# femtoBeacon-BT5_r1_0_1.net
KiCad netlist of a schematic drawn in EAGLE
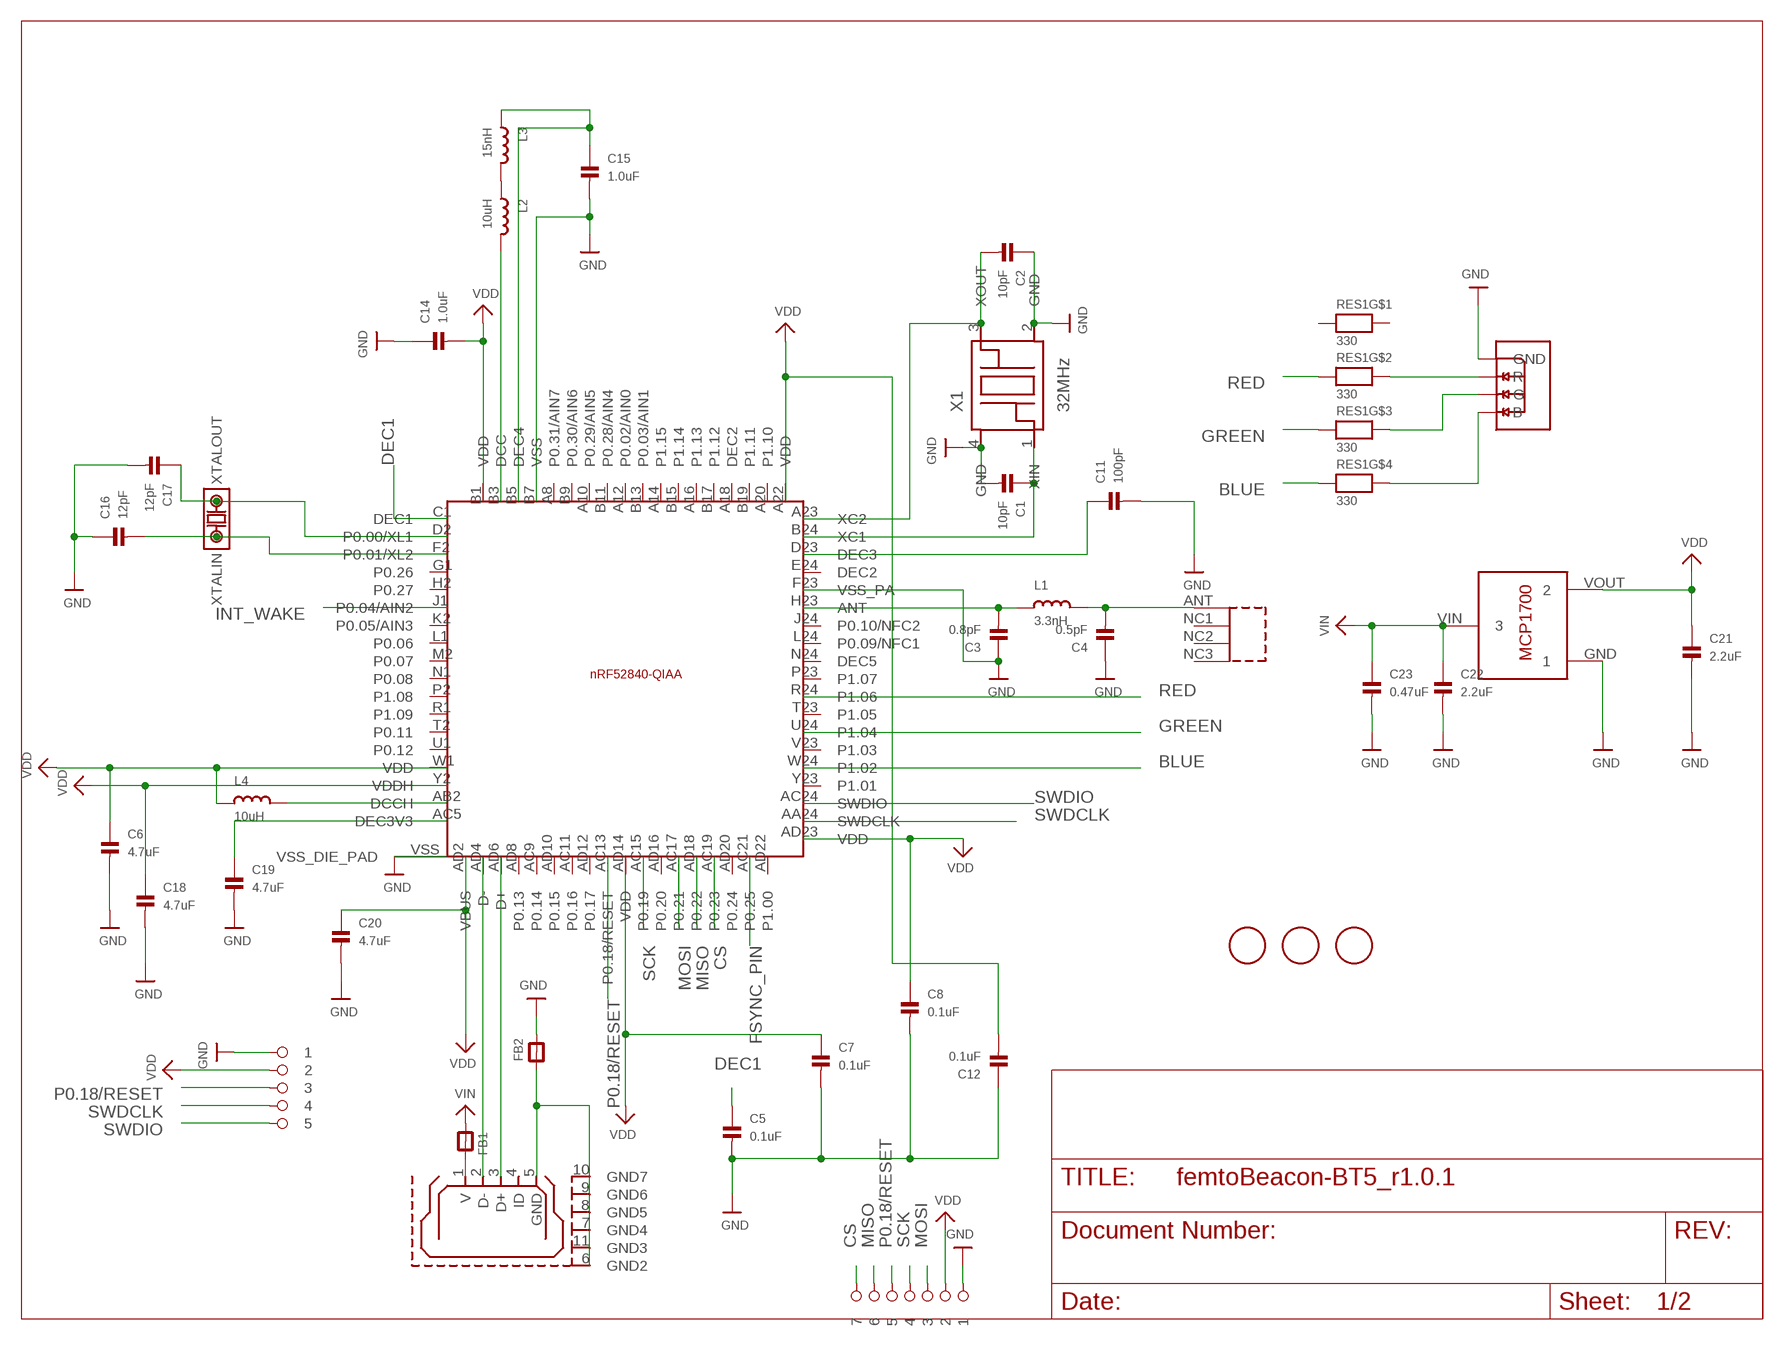
[diagram p0: schematic, sheet 1]
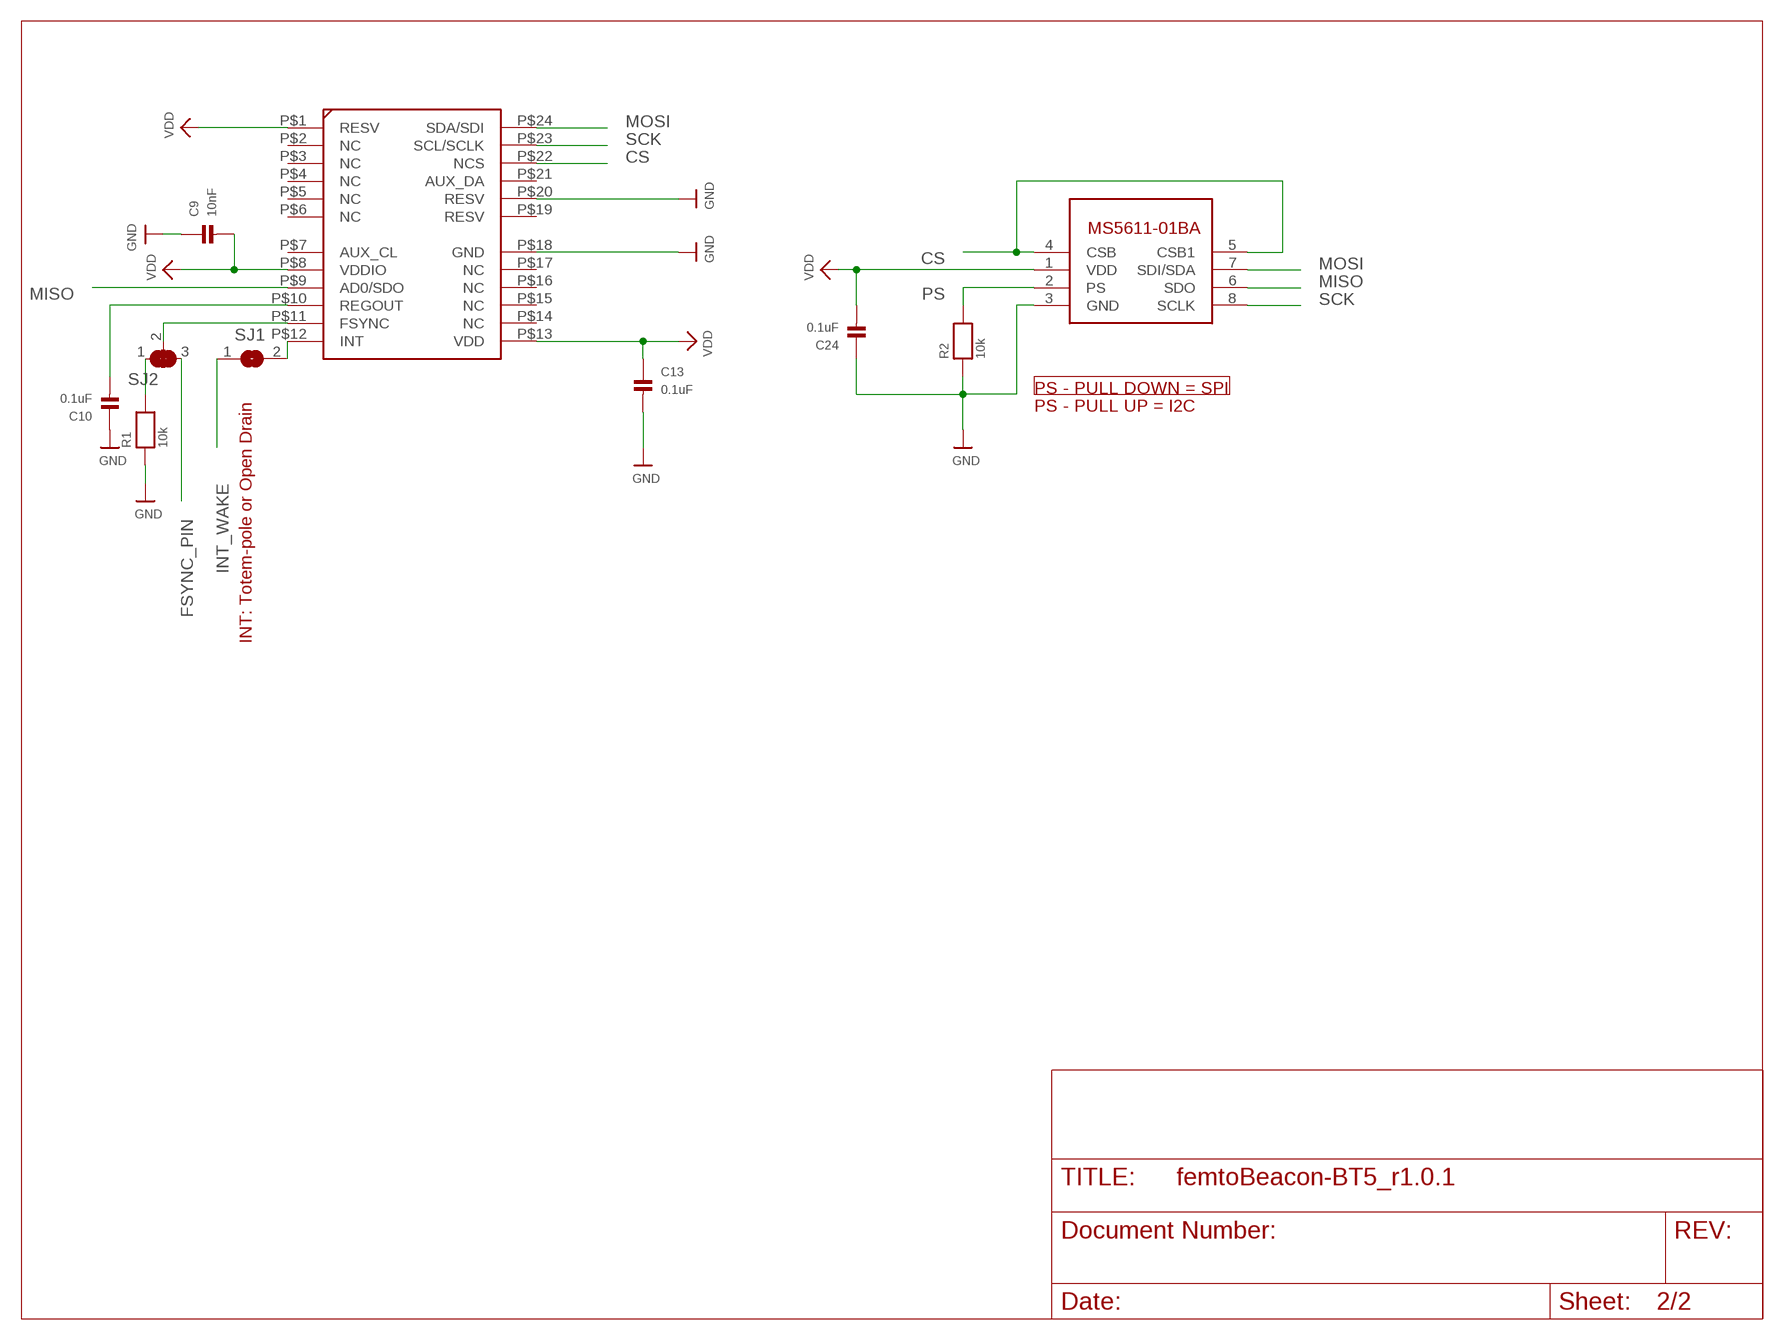
[diagram p1: schematic, sheet 2]

(export (version "E")
  (design (tool "Eeschema 10.0.6"))
  (components
    (comp (ref "ANT")
      (value "0479480001")
      (footprint "eagle-import:0479480001")
      (libsource (lib "eagle-import") (part "0479480001"))
    )
    (comp (ref "C1")
      (value "10pF")
      (footprint "eagle-import:_0402MP")
      (libsource (lib "eagle-import") (part "CAP_CERAMIC_0402MP"))
    )
    (comp (ref "C2")
      (value "10pF")
      (footprint "eagle-import:_0402MP")
      (libsource (lib "eagle-import") (part "CAP_CERAMIC_0402MP"))
    )
    (comp (ref "C3")
      (value "0.8pF")
      (footprint "eagle-import:_0402MP")
      (libsource (lib "eagle-import") (part "CAP_CERAMIC_0402MP"))
    )
    (comp (ref "C4")
      (value "0.5pF")
      (footprint "eagle-import:_0402MP")
      (libsource (lib "eagle-import") (part "CAP_CERAMIC_0402MP"))
    )
    (comp (ref "C5")
      (value "0.1uF")
      (footprint "eagle-import:_0402MP")
      (libsource (lib "eagle-import") (part "CAP_CERAMIC_0402MP"))
    )
    (comp (ref "C6")
      (value "4.7uF")
      (footprint "eagle-import:_0402MP")
      (libsource (lib "eagle-import") (part "CAP_CERAMIC_0402MP"))
    )
    (comp (ref "C7")
      (value "0.1uF")
      (footprint "eagle-import:_0402MP")
      (libsource (lib "eagle-import") (part "CAP_CERAMIC_0402MP"))
    )
    (comp (ref "C8")
      (value "0.1uF")
      (footprint "eagle-import:_0402MP")
      (libsource (lib "eagle-import") (part "CAP_CERAMIC_0402MP"))
    )
    (comp (ref "C11")
      (value "100pF")
      (footprint "eagle-import:_0402MP")
      (libsource (lib "eagle-import") (part "CAP_CERAMIC_0402MP"))
    )
    (comp (ref "C12")
      (value "0.1uF")
      (footprint "eagle-import:_0402MP")
      (libsource (lib "eagle-import") (part "CAP_CERAMIC_0402MP"))
    )
    (comp (ref "C14")
      (value "1.0uF")
      (footprint "eagle-import:_0402MP")
      (libsource (lib "eagle-import") (part "CAP_CERAMIC_0402MP"))
    )
    (comp (ref "C15")
      (value "1.0uF")
      (footprint "eagle-import:_0402MP")
      (libsource (lib "eagle-import") (part "CAP_CERAMIC_0402MP"))
    )
    (comp (ref "C16")
      (value "12pF")
      (footprint "eagle-import:_0402MP")
      (libsource (lib "eagle-import") (part "CAP_CERAMIC_0402MP"))
    )
    (comp (ref "C17")
      (value "12pF")
      (footprint "eagle-import:_0402MP")
      (libsource (lib "eagle-import") (part "CAP_CERAMIC_0402MP"))
    )
    (comp (ref "C18")
      (value "4.7uF")
      (footprint "eagle-import:_0402MP")
      (libsource (lib "eagle-import") (part "CAP_CERAMIC_0402MP"))
    )
    (comp (ref "C19")
      (value "4.7uF")
      (footprint "eagle-import:_0402MP")
      (libsource (lib "eagle-import") (part "CAP_CERAMIC_0402MP"))
    )
    (comp (ref "C20")
      (value "4.7uF")
      (footprint "eagle-import:_0402MP")
      (libsource (lib "eagle-import") (part "CAP_CERAMIC_0402MP"))
    )
    (comp (ref "C21")
      (value "2.2uF")
      (footprint "eagle-import:_0402MP")
      (libsource (lib "eagle-import") (part "CAP_CERAMIC_0402MP"))
    )
    (comp (ref "C22")
      (value "2.2uF")
      (footprint "eagle-import:_0402MP")
      (libsource (lib "eagle-import") (part "CAP_CERAMIC_0402MP"))
    )
    (comp (ref "C23")
      (value "0.47uF")
      (footprint "eagle-import:_0402MP")
      (libsource (lib "eagle-import") (part "CAP_CERAMIC_0402MP"))
    )
    (comp (ref "FB1")
      (value "FERRITE_0603MP")
      (footprint "eagle-import:_0603MP")
      (libsource (lib "eagle-import") (part "FERRITE_0603MP"))
    )
    (comp (ref "FB2")
      (value "FERRITE_0603MP")
      (footprint "eagle-import:_0603MP")
      (libsource (lib "eagle-import") (part "FERRITE_0603MP"))
    )
    (comp (ref "FID1")
      (value "FIDUCIAL")
      (footprint "eagle-import:FIDUCIAL_1MM")
      (libsource (lib "eagle-import") (part "FIDUCIAL"))
    )
    (comp (ref "FID2")
      (value "FIDUCIAL")
      (footprint "eagle-import:FIDUCIAL_1MM")
      (libsource (lib "eagle-import") (part "FIDUCIAL"))
    )
    (comp (ref "FID3")
      (value "FIDUCIAL")
      (footprint "eagle-import:FIDUCIAL_1MM")
      (libsource (lib "eagle-import") (part "FIDUCIAL"))
    )
    (comp (ref "IC")
      (value "NRF52840")
      (footprint "eagle-import:NRF52840")
      (libsource (lib "eagle-import") (part "NRF52840"))
    )
    (comp (ref "L1")
      (value "3.3nH")
      (footprint "eagle-import:_0402MP")
      (libsource (lib "eagle-import") (part "INDUCTOR_0402MP"))
    )
    (comp (ref "L2")
      (value "10uH")
      (footprint "eagle-import:_0402MP")
      (libsource (lib "eagle-import") (part "INDUCTOR_0402MP"))
    )
    (comp (ref "L3")
      (value "15nH")
      (footprint "eagle-import:_0402MP")
      (libsource (lib "eagle-import") (part "INDUCTOR_0402MP"))
    )
    (comp (ref "L4")
      (value "10uH")
      (footprint "eagle-import:_0402MP")
      (libsource (lib "eagle-import") (part "INDUCTOR_0402MP"))
    )
    (comp (ref "LDO_VREG")
      (value "MCP1700T-3302E/TT")
      (footprint "eagle-import:MCP1700T-3302E_TT")
      (libsource (lib "eagle-import") (part "MCP1700T-3302E/TT"))
    )
    (comp (ref "RES1")
      (value "330")
      (footprint "eagle-import:RESPACK_4X0603")
      (fields (field (name "MFN_ID") "741C083331JP"))
      (libsource (lib "eagle-import") (part "RESISTOR_4PACK"))
    )
    (comp (ref "U$1")
      (value "1X5_ROUND")
      (footprint "eagle-import:1X5_ROUND")
      (libsource (lib "eagle-import") (part "1X5_ROUND"))
    )
    (comp (ref "U$7")
      (value "LRTB_R48G")
      (footprint "eagle-import:LRTB_R48G")
      (libsource (lib "eagle-import") (part "LRTB_R48G"))
    )
    (comp (ref "U$27")
      (value "1X7_ROUND")
      (footprint "eagle-import:1X7_ROUND")
      (libsource (lib "eagle-import") (part "1X7_ROUND"))
    )
    (comp (ref "USB")
      (value "USB_MICROB")
      (footprint "eagle-import:USB_MICROB_PACKAGE")
      (libsource (lib "eagle-import") (part "USB_MICROB"))
    )
    (comp (ref "X1")
      (value "32MHz")
      (footprint "eagle-import:FA-128")
      (libsource (lib "eagle-import") (part "FA-128"))
    )
    (comp (ref "X2")
      (value "32.768kHZ")
      (footprint "eagle-import:ABS06-107-32.768KHZ-T")
      (libsource (lib "eagle-import") (part "ABS06-107-32.768KHZ-T"))
    )
    (comp (ref "BARO")
      (value "MS5611-01BA03")
      (footprint "eagle-import:MS5611-01BA03")
      (libsource (lib "eagle-import") (part "MS5611-01BA03"))
    )
    (comp (ref "C9")
      (value "10nF")
      (footprint "eagle-import:_0402MP")
      (libsource (lib "eagle-import") (part "CAP_CERAMIC_0402MP"))
    )
    (comp (ref "C10")
      (value "0.1uF")
      (footprint "eagle-import:_0402MP")
      (libsource (lib "eagle-import") (part "CAP_CERAMIC_0402MP"))
    )
    (comp (ref "C13")
      (value "0.1uF")
      (footprint "eagle-import:_0402MP")
      (libsource (lib "eagle-import") (part "CAP_CERAMIC_0402MP"))
    )
    (comp (ref "C24")
      (value "0.1uF")
      (footprint "eagle-import:_0402MP")
      (libsource (lib "eagle-import") (part "CAP_CERAMIC_0402MP"))
    )
    (comp (ref "IMU")
      (value "MPU-9250")
      (footprint "eagle-import:QFN_3X3MM")
      (libsource (lib "eagle-import") (part "MPU-9250"))
    )
    (comp (ref "R1")
      (value "10k")
      (footprint "eagle-import:_0402MP")
      (libsource (lib "eagle-import") (part "RESISTOR_0402MP"))
    )
    (comp (ref "R2")
      (value "10k")
      (footprint "eagle-import:_0402MP")
      (libsource (lib "eagle-import") (part "RESISTOR_0402MP"))
    )
    (comp (ref "SJ1")
      (value "SOLDERJUMPERCLOSED")
      (footprint "eagle-import:SOLDERJUMPER_CLOSEDWIRE")
      (libsource (lib "eagle-import") (part "SOLDERJUMPERCLOSED"))
    )
    (comp (ref "SJ2")
      (value "SOLDERJUMPER_2WAY")
      (footprint "eagle-import:SOLDERJUMPER_2WAY_OPEN_NOPASTE")
      (libsource (lib "eagle-import") (part "SOLDERJUMPER_2WAY"))
    )
  )
  (nets
    (net (code "1") (name "BLUE") (class "Default")
      (node (ref "IC") (pin "W24") (pinfunction "P1.02_W24") (pintype "bidirectional"))
      (node (ref "RES1") (pin "4") (pinfunction "1_4") (pintype "passive"))
    )
    (net (code "2") (name "CS") (class "Default")
      (node (ref "BARO") (pin "4") (pinfunction "CSB_4") (pintype "bidirectional"))
      (node (ref "BARO") (pin "5") (pinfunction "CSB1_5") (pintype "bidirectional"))
      (node (ref "IC") (pin "AC19") (pinfunction "P0.23_AC19") (pintype "bidirectional"))
      (node (ref "IMU") (pin "P$22") (pinfunction "NCS_P$22") (pintype "bidirectional"))
      (node (ref "U$27") (pin "P$7") (pinfunction "7_P$7") (pintype "bidirectional"))
    )
    (net (code "3") (name "DEC1") (class "Default")
      (node (ref "C5") (pin "1") (pinfunction "P$1_1") (pintype "passive"))
      (node (ref "IC") (pin "C1") (pinfunction "DEC1_C1") (pintype "bidirectional"))
    )
    (net (code "4") (name "FSYNC_PIN") (class "Default")
      (node (ref "IC") (pin "AC21") (pinfunction "P0.25_AC21") (pintype "bidirectional"))
      (node (ref "SJ2") (pin "3") (pinfunction "3_3") (pintype "passive"))
    )
    (net (code "5") (name "GND") (class "Default")
      (node (ref "BARO") (pin "3") (pinfunction "GND_3") (pintype "bidirectional"))
      (node (ref "C1") (pin "2") (pinfunction "P$2_2") (pintype "passive"))
      (node (ref "C10") (pin "1") (pinfunction "P$1_1") (pintype "passive"))
      (node (ref "C11") (pin "2") (pinfunction "P$2_2") (pintype "passive"))
      (node (ref "C12") (pin "1") (pinfunction "P$1_1") (pintype "passive"))
      (node (ref "C13") (pin "2") (pinfunction "P$2_2") (pintype "passive"))
      (node (ref "C14") (pin "1") (pinfunction "P$1_1") (pintype "passive"))
      (node (ref "C15") (pin "2") (pinfunction "P$2_2") (pintype "passive"))
      (node (ref "C16") (pin "1") (pinfunction "P$1_1") (pintype "passive"))
      (node (ref "C17") (pin "2") (pinfunction "P$2_2") (pintype "passive"))
      (node (ref "C18") (pin "2") (pinfunction "P$2_2") (pintype "passive"))
      (node (ref "C19") (pin "2") (pinfunction "P$2_2") (pintype "passive"))
      (node (ref "C2") (pin "1") (pinfunction "P$1_1") (pintype "passive"))
      (node (ref "C20") (pin "2") (pinfunction "P$2_2") (pintype "passive"))
      (node (ref "C21") (pin "2") (pinfunction "P$2_2") (pintype "passive"))
      (node (ref "C22") (pin "2") (pinfunction "P$2_2") (pintype "passive"))
      (node (ref "C23") (pin "2") (pinfunction "P$2_2") (pintype "passive"))
      (node (ref "C24") (pin "1") (pinfunction "P$1_1") (pintype "passive"))
      (node (ref "C3") (pin "1") (pinfunction "P$1_1") (pintype "passive"))
      (node (ref "C4") (pin "1") (pinfunction "P$1_1") (pintype "passive"))
      (node (ref "C5") (pin "2") (pinfunction "P$2_2") (pintype "passive"))
      (node (ref "C6") (pin "2") (pinfunction "P$2_2") (pintype "passive"))
      (node (ref "C7") (pin "2") (pinfunction "P$2_2") (pintype "passive"))
      (node (ref "C8") (pin "2") (pinfunction "P$2_2") (pintype "passive"))
      (node (ref "C9") (pin "1") (pinfunction "P$1_1") (pintype "passive"))
      (node (ref "FB2") (pin "2") (pinfunction "P$2_2") (pintype "passive"))
      (node (ref "IC") (pin "B7") (pinfunction "VSS_B7") (pintype "bidirectional"))
      (node (ref "IC") (pin "F23") (pinfunction "VSS_PA_F23") (pintype "bidirectional"))
      (node (ref "IC") (pin "VSS") (pinfunction "VSS_DIE_PAD_VSS") (pintype "bidirectional"))
      (node (ref "IMU") (pin "P$18") (pinfunction "GND_P$18") (pintype "bidirectional"))
      (node (ref "IMU") (pin "P$20") (pinfunction "RESV_P$20") (pintype "bidirectional"))
      (node (ref "LDO_VREG") (pin "GND") (pinfunction "1_GND") (pintype "bidirectional"))
      (node (ref "R1") (pin "1") (pinfunction "1_1") (pintype "passive"))
      (node (ref "R2") (pin "1") (pinfunction "1_1") (pintype "passive"))
      (node (ref "U$1") (pin "P$1") (pinfunction "1_P$1") (pintype "bidirectional"))
      (node (ref "U$27") (pin "P$1") (pinfunction "1_P$1") (pintype "bidirectional"))
      (node (ref "U$7") (pin "1") (pinfunction "GND_1") (pintype "bidirectional"))
      (node (ref "X1") (pin "2") (pinfunction "GND_2") (pintype "bidirectional"))
      (node (ref "X1") (pin "4") (pinfunction "GND_4") (pintype "bidirectional"))
    )
    (net (code "6") (name "GREEN") (class "Default")
      (node (ref "IC") (pin "U24") (pinfunction "P1.04_U24") (pintype "bidirectional"))
      (node (ref "RES1") (pin "3") (pinfunction "1_3") (pintype "passive"))
    )
    (net (code "7") (name "INT_WAKE") (class "Default")
      (node (ref "IC") (pin "J1") (pinfunction "P0.04/AIN2_J1") (pintype "bidirectional"))
      (node (ref "SJ1") (pin "1") (pinfunction "1_1") (pintype "passive"))
    )
    (net (code "8") (name "MISO") (class "Default")
      (node (ref "BARO") (pin "6") (pinfunction "SDO_6") (pintype "bidirectional"))
      (node (ref "IC") (pin "AD18") (pinfunction "P0.22_AD18") (pintype "bidirectional"))
      (node (ref "IMU") (pin "P$9") (pinfunction "AD0/SDO_P$9") (pintype "bidirectional"))
      (node (ref "U$27") (pin "P$6") (pinfunction "6_P$6") (pintype "bidirectional"))
    )
    (net (code "9") (name "MOSI") (class "Default")
      (node (ref "BARO") (pin "7") (pinfunction "SDI/SDA_7") (pintype "bidirectional"))
      (node (ref "IC") (pin "AC17") (pinfunction "P0.21_AC17") (pintype "bidirectional"))
      (node (ref "IMU") (pin "P$24") (pinfunction "SDA/SDI_P$24") (pintype "bidirectional"))
      (node (ref "U$27") (pin "P$3") (pinfunction "3_P$3") (pintype "bidirectional"))
    )
    (net (code "10") (name "Net-(ANT-1)") (class "Default")
      (node (ref "ANT") (pin "ANT") (pinfunction "1_ANT") (pintype "bidirectional"))
      (node (ref "C4") (pin "2") (pinfunction "P$2_2") (pintype "passive"))
      (node (ref "L1") (pin "2") (pinfunction "2_2") (pintype "passive"))
    )
    (net (code "11") (name "Net-(C1-P$1)") (class "Default")
      (node (ref "C1") (pin "1") (pinfunction "P$1_1") (pintype "passive"))
      (node (ref "IC") (pin "B24") (pinfunction "XC1_B24") (pintype "bidirectional"))
      (node (ref "X1") (pin "1") (pinfunction "XIN_1") (pintype "bidirectional"))
    )
    (net (code "12") (name "Net-(C2-P$2)") (class "Default")
      (node (ref "C2") (pin "2") (pinfunction "P$2_2") (pintype "passive"))
      (node (ref "IC") (pin "A23") (pinfunction "XC2_A23") (pintype "bidirectional"))
      (node (ref "X1") (pin "3") (pinfunction "XOUT_3") (pintype "bidirectional"))
    )
    (net (code "13") (name "Net-(C3-P$2)") (class "Default")
      (node (ref "C3") (pin "2") (pinfunction "P$2_2") (pintype "passive"))
      (node (ref "IC") (pin "H23") (pinfunction "ANT_H23") (pintype "bidirectional"))
      (node (ref "L1") (pin "1") (pinfunction "1_1") (pintype "passive"))
    )
    (net (code "14") (name "Net-(C10-P$2)") (class "Default")
      (node (ref "C10") (pin "2") (pinfunction "P$2_2") (pintype "passive"))
      (node (ref "IMU") (pin "P$10") (pinfunction "REGOUT_P$10") (pintype "bidirectional"))
    )
    (net (code "15") (name "Net-(C11-P$1)") (class "Default")
      (node (ref "C11") (pin "1") (pinfunction "P$1_1") (pintype "passive"))
      (node (ref "IC") (pin "D23") (pinfunction "DEC3_D23") (pintype "bidirectional"))
    )
    (net (code "16") (name "Net-(C15-P$1)") (class "Default")
      (node (ref "C15") (pin "1") (pinfunction "P$1_1") (pintype "passive"))
      (node (ref "IC") (pin "B5") (pinfunction "DEC4_B5") (pintype "bidirectional"))
      (node (ref "L3") (pin "1") (pinfunction "1_1") (pintype "passive"))
    )
    (net (code "17") (name "Net-(C16-P$2)") (class "Default")
      (node (ref "C16") (pin "2") (pinfunction "P$2_2") (pintype "passive"))
      (node (ref "IC") (pin "F2") (pinfunction "P0.01/XL2_F2") (pintype "bidirectional"))
      (node (ref "X2") (pin "1") (pinfunction "XTALIN_1") (pintype "bidirectional"))
    )
    (net (code "18") (name "Net-(C17-P$1)") (class "Default")
      (node (ref "C17") (pin "1") (pinfunction "P$1_1") (pintype "passive"))
      (node (ref "IC") (pin "D2") (pinfunction "P0.00/XL1_D2") (pintype "bidirectional"))
      (node (ref "X2") (pin "2") (pinfunction "XTALOUT_2") (pintype "bidirectional"))
    )
    (net (code "19") (name "Net-(C19-P$1)") (class "Default")
      (node (ref "C19") (pin "1") (pinfunction "P$1_1") (pintype "passive"))
      (node (ref "IC") (pin "AC5") (pinfunction "DEC3V3_AC5") (pintype "bidirectional"))
    )
    (net (code "20") (name "Net-(FB1-P$2)") (class "Default")
      (node (ref "FB1") (pin "2") (pinfunction "P$2_2") (pintype "passive"))
      (node (ref "USB") (pin "1") (pinfunction "V_1") (pintype "bidirectional"))
    )
    (net (code "21") (name "Net-(FB2-P$1)") (class "Default")
      (node (ref "FB2") (pin "1") (pinfunction "P$1_1") (pintype "passive"))
      (node (ref "USB") (pin "10") (pinfunction "GND7_10") (pintype "bidirectional"))
      (node (ref "USB") (pin "11") (pinfunction "GND3_11") (pintype "bidirectional"))
      (node (ref "USB") (pin "5") (pinfunction "GND_5") (pintype "bidirectional"))
      (node (ref "USB") (pin "6") (pinfunction "GND2_6") (pintype "bidirectional"))
      (node (ref "USB") (pin "7") (pinfunction "GND4_7") (pintype "bidirectional"))
      (node (ref "USB") (pin "8") (pinfunction "GND5_8") (pintype "bidirectional"))
      (node (ref "USB") (pin "9") (pinfunction "GND6_9") (pintype "bidirectional"))
    )
    (net (code "22") (name "Net-(IC-D+)") (class "Default")
      (node (ref "IC") (pin "AD6") (pinfunction "D+_AD6") (pintype "bidirectional"))
      (node (ref "USB") (pin "3") (pinfunction "D+_3") (pintype "bidirectional"))
    )
    (net (code "23") (name "Net-(IC-D-)") (class "Default")
      (node (ref "IC") (pin "AD4") (pinfunction "D-_AD4") (pintype "bidirectional"))
      (node (ref "USB") (pin "2") (pinfunction "D-_2") (pintype "bidirectional"))
    )
    (net (code "24") (name "Net-(IC-DCC)") (class "Default")
      (node (ref "IC") (pin "B3") (pinfunction "DCC_B3") (pintype "bidirectional"))
      (node (ref "L2") (pin "2") (pinfunction "2_2") (pintype "passive"))
    )
    (net (code "25") (name "Net-(IC-DCCH)") (class "Default")
      (node (ref "IC") (pin "AB2") (pinfunction "DCCH_AB2") (pintype "bidirectional"))
      (node (ref "L4") (pin "2") (pinfunction "2_2") (pintype "passive"))
    )
    (net (code "26") (name "Net-(IMU-FSYNC)") (class "Default")
      (node (ref "IMU") (pin "P$11") (pinfunction "FSYNC_P$11") (pintype "bidirectional"))
      (node (ref "SJ2") (pin "2") (pinfunction "2_2") (pintype "passive"))
    )
    (net (code "27") (name "Net-(IMU-INT)") (class "Default")
      (node (ref "IMU") (pin "P$12") (pinfunction "INT_P$12") (pintype "bidirectional"))
      (node (ref "SJ1") (pin "2") (pinfunction "2_2") (pintype "passive"))
    )
    (net (code "28") (name "Net-(L2-Pad1)") (class "Default")
      (node (ref "L2") (pin "1") (pinfunction "1_1") (pintype "passive"))
      (node (ref "L3") (pin "2") (pinfunction "2_2") (pintype "passive"))
    )
    (net (code "29") (name "Net-(R1-Pad2)") (class "Default")
      (node (ref "R1") (pin "2") (pinfunction "2_2") (pintype "passive"))
      (node (ref "SJ2") (pin "1") (pinfunction "1_1") (pintype "passive"))
    )
    (net (code "30") (name "Net-(RES1B-2)") (class "Default")
      (node (ref "RES1") (pin "7") (pinfunction "2_7") (pintype "passive"))
      (node (ref "U$7") (pin "2") (pinfunction "R_2") (pintype "bidirectional"))
    )
    (net (code "31") (name "Net-(RES1C-2)") (class "Default")
      (node (ref "RES1") (pin "6") (pinfunction "2_6") (pintype "passive"))
      (node (ref "U$7") (pin "3") (pinfunction "G_3") (pintype "bidirectional"))
    )
    (net (code "32") (name "Net-(RES1D-2)") (class "Default")
      (node (ref "RES1") (pin "5") (pinfunction "2_5") (pintype "passive"))
      (node (ref "U$7") (pin "4") (pinfunction "B_4") (pintype "bidirectional"))
    )
    (net (code "33") (name "P0.18{slash}RESET") (class "Default")
      (node (ref "IC") (pin "AC13") (pinfunction "P0.18/RESET_AC13") (pintype "bidirectional"))
      (node (ref "U$1") (pin "P$3") (pinfunction "3_P$3") (pintype "bidirectional"))
      (node (ref "U$27") (pin "P$5") (pinfunction "5_P$5") (pintype "bidirectional"))
    )
    (net (code "34") (name "PS") (class "Default")
      (node (ref "BARO") (pin "2") (pinfunction "PS_2") (pintype "bidirectional"))
      (node (ref "R2") (pin "2") (pinfunction "2_2") (pintype "passive"))
    )
    (net (code "35") (name "RED") (class "Default")
      (node (ref "IC") (pin "R24") (pinfunction "P1.06_R24") (pintype "bidirectional"))
      (node (ref "RES1") (pin "2") (pinfunction "1_2") (pintype "passive"))
    )
    (net (code "36") (name "SCK") (class "Default")
      (node (ref "BARO") (pin "8") (pinfunction "SCLK_8") (pintype "bidirectional"))
      (node (ref "IC") (pin "AC15") (pinfunction "P0.19_AC15") (pintype "bidirectional"))
      (node (ref "IMU") (pin "P$23") (pinfunction "SCL/SCLK_P$23") (pintype "bidirectional"))
      (node (ref "U$27") (pin "P$4") (pinfunction "4_P$4") (pintype "bidirectional"))
    )
    (net (code "37") (name "SWDCLK") (class "Default")
      (node (ref "IC") (pin "AA24") (pinfunction "SWDCLK_AA24") (pintype "bidirectional"))
      (node (ref "U$1") (pin "P$4") (pinfunction "4_P$4") (pintype "bidirectional"))
    )
    (net (code "38") (name "SWDIO") (class "Default")
      (node (ref "IC") (pin "AC24") (pinfunction "SWDIO_AC24") (pintype "bidirectional"))
      (node (ref "U$1") (pin "P$5") (pinfunction "5_P$5") (pintype "bidirectional"))
    )
    (net (code "39") (name "VDD") (class "Default")
      (node (ref "BARO") (pin "1") (pinfunction "VDD_1") (pintype "bidirectional"))
      (node (ref "C12") (pin "2") (pinfunction "P$2_2") (pintype "passive"))
      (node (ref "C13") (pin "1") (pinfunction "P$1_1") (pintype "passive"))
      (node (ref "C14") (pin "2") (pinfunction "P$2_2") (pintype "passive"))
      (node (ref "C18") (pin "1") (pinfunction "P$1_1") (pintype "passive"))
      (node (ref "C20") (pin "1") (pinfunction "P$1_1") (pintype "passive"))
      (node (ref "C21") (pin "1") (pinfunction "P$1_1") (pintype "passive"))
      (node (ref "C24") (pin "2") (pinfunction "P$2_2") (pintype "passive"))
      (node (ref "C6") (pin "1") (pinfunction "P$1_1") (pintype "passive"))
      (node (ref "C7") (pin "1") (pinfunction "P$1_1") (pintype "passive"))
      (node (ref "C8") (pin "1") (pinfunction "P$1_1") (pintype "passive"))
      (node (ref "C9") (pin "2") (pinfunction "P$2_2") (pintype "passive"))
      (node (ref "IC") (pin "A22") (pinfunction "VDD_A22") (pintype "bidirectional"))
      (node (ref "IC") (pin "AD14") (pinfunction "VDD_AD14") (pintype "bidirectional"))
      (node (ref "IC") (pin "AD2") (pinfunction "VBUS_AD2") (pintype "bidirectional"))
      (node (ref "IC") (pin "AD23") (pinfunction "VDD_AD23") (pintype "bidirectional"))
      (node (ref "IC") (pin "B1") (pinfunction "VDD_B1") (pintype "bidirectional"))
      (node (ref "IC") (pin "W1") (pinfunction "VDD_W1") (pintype "bidirectional"))
      (node (ref "IC") (pin "Y2") (pinfunction "VDDH_Y2") (pintype "bidirectional"))
      (node (ref "IMU") (pin "P$1") (pinfunction "RESV_P$1") (pintype "bidirectional"))
      (node (ref "IMU") (pin "P$13") (pinfunction "VDD_P$13") (pintype "bidirectional"))
      (node (ref "IMU") (pin "P$8") (pinfunction "VDDIO_P$8") (pintype "bidirectional"))
      (node (ref "L4") (pin "1") (pinfunction "1_1") (pintype "passive"))
      (node (ref "LDO_VREG") (pin "VOUT") (pinfunction "2_VOUT") (pintype "bidirectional"))
      (node (ref "U$1") (pin "P$2") (pinfunction "2_P$2") (pintype "bidirectional"))
      (node (ref "U$27") (pin "P$2") (pinfunction "2_P$2") (pintype "bidirectional"))
    )
    (net (code "40") (name "VIN") (class "Default")
      (node (ref "C22") (pin "1") (pinfunction "P$1_1") (pintype "passive"))
      (node (ref "C23") (pin "1") (pinfunction "P$1_1") (pintype "passive"))
      (node (ref "FB1") (pin "1") (pinfunction "P$1_1") (pintype "passive"))
      (node (ref "LDO_VREG") (pin "VIN") (pinfunction "3_VIN") (pintype "bidirectional"))
    )
    (net (code "41") (name "unconnected-(ANT-2-PadNC1)") (class "Default")
      (node (ref "ANT") (pin "NC1") (pinfunction "2_NC1") (pintype "bidirectional"))
    )
    (net (code "42") (name "unconnected-(ANT-3-PadNC2)") (class "Default")
      (node (ref "ANT") (pin "NC2") (pinfunction "3_NC2") (pintype "bidirectional"))
    )
    (net (code "43") (name "unconnected-(ANT-4-PadNC3)") (class "Default")
      (node (ref "ANT") (pin "NC3") (pinfunction "4_NC3") (pintype "bidirectional"))
    )
    (net (code "44") (name "unconnected-(IC-DEC2-PadA18)") (class "Default")
      (node (ref "IC") (pin "A18") (pinfunction "DEC2_A18") (pintype "bidirectional"))
    )
    (net (code "45") (name "unconnected-(IC-DEC2-PadE24)") (class "Default")
      (node (ref "IC") (pin "E24") (pinfunction "DEC2_E24") (pintype "bidirectional"))
    )
    (net (code "46") (name "unconnected-(IC-DEC5-PadN24)") (class "Default")
      (node (ref "IC") (pin "N24") (pinfunction "DEC5_N24") (pintype "bidirectional"))
    )
    (net (code "47") (name "unconnected-(IC-P0.02{slash}AIN0-PadA12)") (class "Default")
      (node (ref "IC") (pin "A12") (pinfunction "P0.02/AIN0_A12") (pintype "bidirectional"))
    )
    (net (code "48") (name "unconnected-(IC-P0.03{slash}AIN1-PadB13)") (class "Default")
      (node (ref "IC") (pin "B13") (pinfunction "P0.03/AIN1_B13") (pintype "bidirectional"))
    )
    (net (code "49") (name "unconnected-(IC-P0.05{slash}AIN3-PadK2)") (class "Default")
      (node (ref "IC") (pin "K2") (pinfunction "P0.05/AIN3_K2") (pintype "bidirectional"))
    )
    (net (code "50") (name "unconnected-(IC-P0.06-PadL1)") (class "Default")
      (node (ref "IC") (pin "L1") (pinfunction "P0.06_L1") (pintype "bidirectional"))
    )
    (net (code "51") (name "unconnected-(IC-P0.07-PadM2)") (class "Default")
      (node (ref "IC") (pin "M2") (pinfunction "P0.07_M2") (pintype "bidirectional"))
    )
    (net (code "52") (name "unconnected-(IC-P0.08-PadN1)") (class "Default")
      (node (ref "IC") (pin "N1") (pinfunction "P0.08_N1") (pintype "bidirectional"))
    )
    (net (code "53") (name "unconnected-(IC-P0.09{slash}NFC1-PadL24)") (class "Default")
      (node (ref "IC") (pin "L24") (pinfunction "P0.09/NFC1_L24") (pintype "bidirectional"))
    )
    (net (code "54") (name "unconnected-(IC-P0.10{slash}NFC2-PadJ24)") (class "Default")
      (node (ref "IC") (pin "J24") (pinfunction "P0.10/NFC2_J24") (pintype "bidirectional"))
    )
    (net (code "55") (name "unconnected-(IC-P0.11-PadT2)") (class "Default")
      (node (ref "IC") (pin "T2") (pinfunction "P0.11_T2") (pintype "bidirectional"))
    )
    (net (code "56") (name "unconnected-(IC-P0.12-PadU1)") (class "Default")
      (node (ref "IC") (pin "U1") (pinfunction "P0.12_U1") (pintype "bidirectional"))
    )
    (net (code "57") (name "unconnected-(IC-P0.13-PadAD8)") (class "Default")
      (node (ref "IC") (pin "AD8") (pinfunction "P0.13_AD8") (pintype "bidirectional"))
    )
    (net (code "58") (name "unconnected-(IC-P0.14-PadAC9)") (class "Default")
      (node (ref "IC") (pin "AC9") (pinfunction "P0.14_AC9") (pintype "bidirectional"))
    )
    (net (code "59") (name "unconnected-(IC-P0.15-PadAD10)") (class "Default")
      (node (ref "IC") (pin "AD10") (pinfunction "P0.15_AD10") (pintype "bidirectional"))
    )
    (net (code "60") (name "unconnected-(IC-P0.16-PadAC11)") (class "Default")
      (node (ref "IC") (pin "AC11") (pinfunction "P0.16_AC11") (pintype "bidirectional"))
    )
    (net (code "61") (name "unconnected-(IC-P0.17-PadAD12)") (class "Default")
      (node (ref "IC") (pin "AD12") (pinfunction "P0.17_AD12") (pintype "bidirectional"))
    )
    (net (code "62") (name "unconnected-(IC-P0.20-PadAD16)") (class "Default")
      (node (ref "IC") (pin "AD16") (pinfunction "P0.20_AD16") (pintype "bidirectional"))
    )
    (net (code "63") (name "unconnected-(IC-P0.24-PadAD20)") (class "Default")
      (node (ref "IC") (pin "AD20") (pinfunction "P0.24_AD20") (pintype "bidirectional"))
    )
    (net (code "64") (name "unconnected-(IC-P0.26-PadG1)") (class "Default")
      (node (ref "IC") (pin "G1") (pinfunction "P0.26_G1") (pintype "bidirectional"))
    )
    (net (code "65") (name "unconnected-(IC-P0.27-PadH2)") (class "Default")
      (node (ref "IC") (pin "H2") (pinfunction "P0.27_H2") (pintype "bidirectional"))
    )
    (net (code "66") (name "unconnected-(IC-P0.28{slash}AIN4-PadB11)") (class "Default")
      (node (ref "IC") (pin "B11") (pinfunction "P0.28/AIN4_B11") (pintype "bidirectional"))
    )
    (net (code "67") (name "unconnected-(IC-P0.29{slash}AIN5-PadA10)") (class "Default")
      (node (ref "IC") (pin "A10") (pinfunction "P0.29/AIN5_A10") (pintype "bidirectional"))
    )
    (net (code "68") (name "unconnected-(IC-P0.30{slash}AIN6-PadB9)") (class "Default")
      (node (ref "IC") (pin "B9") (pinfunction "P0.30/AIN6_B9") (pintype "bidirectional"))
    )
    (net (code "69") (name "unconnected-(IC-P0.31{slash}AIN7-PadA8)") (class "Default")
      (node (ref "IC") (pin "A8") (pinfunction "P0.31/AIN7_A8") (pintype "bidirectional"))
    )
    (net (code "70") (name "unconnected-(IC-P1.00-PadAD22)") (class "Default")
      (node (ref "IC") (pin "AD22") (pinfunction "P1.00_AD22") (pintype "bidirectional"))
    )
    (net (code "71") (name "unconnected-(IC-P1.01-PadY23)") (class "Default")
      (node (ref "IC") (pin "Y23") (pinfunction "P1.01_Y23") (pintype "bidirectional"))
    )
    (net (code "72") (name "unconnected-(IC-P1.03-PadV23)") (class "Default")
      (node (ref "IC") (pin "V23") (pinfunction "P1.03_V23") (pintype "bidirectional"))
    )
    (net (code "73") (name "unconnected-(IC-P1.05-PadT23)") (class "Default")
      (node (ref "IC") (pin "T23") (pinfunction "P1.05_T23") (pintype "bidirectional"))
    )
    (net (code "74") (name "unconnected-(IC-P1.07-PadP23)") (class "Default")
      (node (ref "IC") (pin "P23") (pinfunction "P1.07_P23") (pintype "bidirectional"))
    )
    (net (code "75") (name "unconnected-(IC-P1.08-PadP2)") (class "Default")
      (node (ref "IC") (pin "P2") (pinfunction "P1.08_P2") (pintype "bidirectional"))
    )
    (net (code "76") (name "unconnected-(IC-P1.09-PadR1)") (class "Default")
      (node (ref "IC") (pin "R1") (pinfunction "P1.09_R1") (pintype "bidirectional"))
    )
    (net (code "77") (name "unconnected-(IC-P1.10-PadA20)") (class "Default")
      (node (ref "IC") (pin "A20") (pinfunction "P1.10_A20") (pintype "bidirectional"))
    )
    (net (code "78") (name "unconnected-(IC-P1.11-PadB19)") (class "Default")
      (node (ref "IC") (pin "B19") (pinfunction "P1.11_B19") (pintype "bidirectional"))
    )
    (net (code "79") (name "unconnected-(IC-P1.12-PadB17)") (class "Default")
      (node (ref "IC") (pin "B17") (pinfunction "P1.12_B17") (pintype "bidirectional"))
    )
    (net (code "80") (name "unconnected-(IC-P1.13-PadA16)") (class "Default")
      (node (ref "IC") (pin "A16") (pinfunction "P1.13_A16") (pintype "bidirectional"))
    )
    (net (code "81") (name "unconnected-(IC-P1.14-PadB15)") (class "Default")
      (node (ref "IC") (pin "B15") (pinfunction "P1.14_B15") (pintype "bidirectional"))
    )
    (net (code "82") (name "unconnected-(IC-P1.15-PadA14)") (class "Default")
      (node (ref "IC") (pin "A14") (pinfunction "P1.15_A14") (pintype "bidirectional"))
    )
    (net (code "83") (name "unconnected-(IMU-AUX_CL-PadP$7)") (class "Default")
      (node (ref "IMU") (pin "P$7") (pinfunction "AUX_CL_P$7") (pintype "bidirectional"))
    )
    (net (code "84") (name "unconnected-(IMU-AUX_DA-PadP$21)") (class "Default")
      (node (ref "IMU") (pin "P$21") (pinfunction "AUX_DA_P$21") (pintype "bidirectional"))
    )
    (net (code "85") (name "unconnected-(IMU-NC-PadP$2)") (class "Default")
      (node (ref "IMU") (pin "P$2") (pinfunction "NC_P$2") (pintype "bidirectional"))
    )
    (net (code "86") (name "unconnected-(IMU-NC-PadP$3)") (class "Default")
      (node (ref "IMU") (pin "P$3") (pinfunction "NC_P$3") (pintype "bidirectional"))
    )
    (net (code "87") (name "unconnected-(IMU-NC-PadP$4)") (class "Default")
      (node (ref "IMU") (pin "P$4") (pinfunction "NC_P$4") (pintype "bidirectional"))
    )
    (net (code "88") (name "unconnected-(IMU-NC-PadP$5)") (class "Default")
      (node (ref "IMU") (pin "P$5") (pinfunction "NC_P$5") (pintype "bidirectional"))
    )
    (net (code "89") (name "unconnected-(IMU-NC-PadP$6)") (class "Default")
      (node (ref "IMU") (pin "P$6") (pinfunction "NC_P$6") (pintype "bidirectional"))
    )
    (net (code "90") (name "unconnected-(IMU-NC-PadP$14)") (class "Default")
      (node (ref "IMU") (pin "P$14") (pinfunction "NC_P$14") (pintype "bidirectional"))
    )
    (net (code "91") (name "unconnected-(IMU-NC-PadP$15)") (class "Default")
      (node (ref "IMU") (pin "P$15") (pinfunction "NC_P$15") (pintype "bidirectional"))
    )
    (net (code "92") (name "unconnected-(IMU-NC-PadP$16)") (class "Default")
      (node (ref "IMU") (pin "P$16") (pinfunction "NC_P$16") (pintype "bidirectional"))
    )
    (net (code "93") (name "unconnected-(IMU-NC-PadP$17)") (class "Default")
      (node (ref "IMU") (pin "P$17") (pinfunction "NC_P$17") (pintype "bidirectional"))
    )
    (net (code "94") (name "unconnected-(IMU-RESV-PadP$19)") (class "Default")
      (node (ref "IMU") (pin "P$19") (pinfunction "RESV_P$19") (pintype "bidirectional"))
    )
    (net (code "95") (name "unconnected-(RES1-Pad1)") (class "Default")
      (node (ref "RES1") (pin "1") (pinfunction "1_1") (pintype "passive"))
    )
    (net (code "96") (name "unconnected-(RES1A-2-Pad8)") (class "Default")
      (node (ref "RES1") (pin "8") (pinfunction "2_8") (pintype "passive"))
    )
    (net (code "97") (name "unconnected-(USB-ID-Pad4)") (class "Default")
      (node (ref "USB") (pin "4") (pinfunction "ID_4") (pintype "bidirectional"))
    )
  )
)
